# SAM_Dispenser_2.net
KiCad netlist of a schematic drawn in Altium Designer
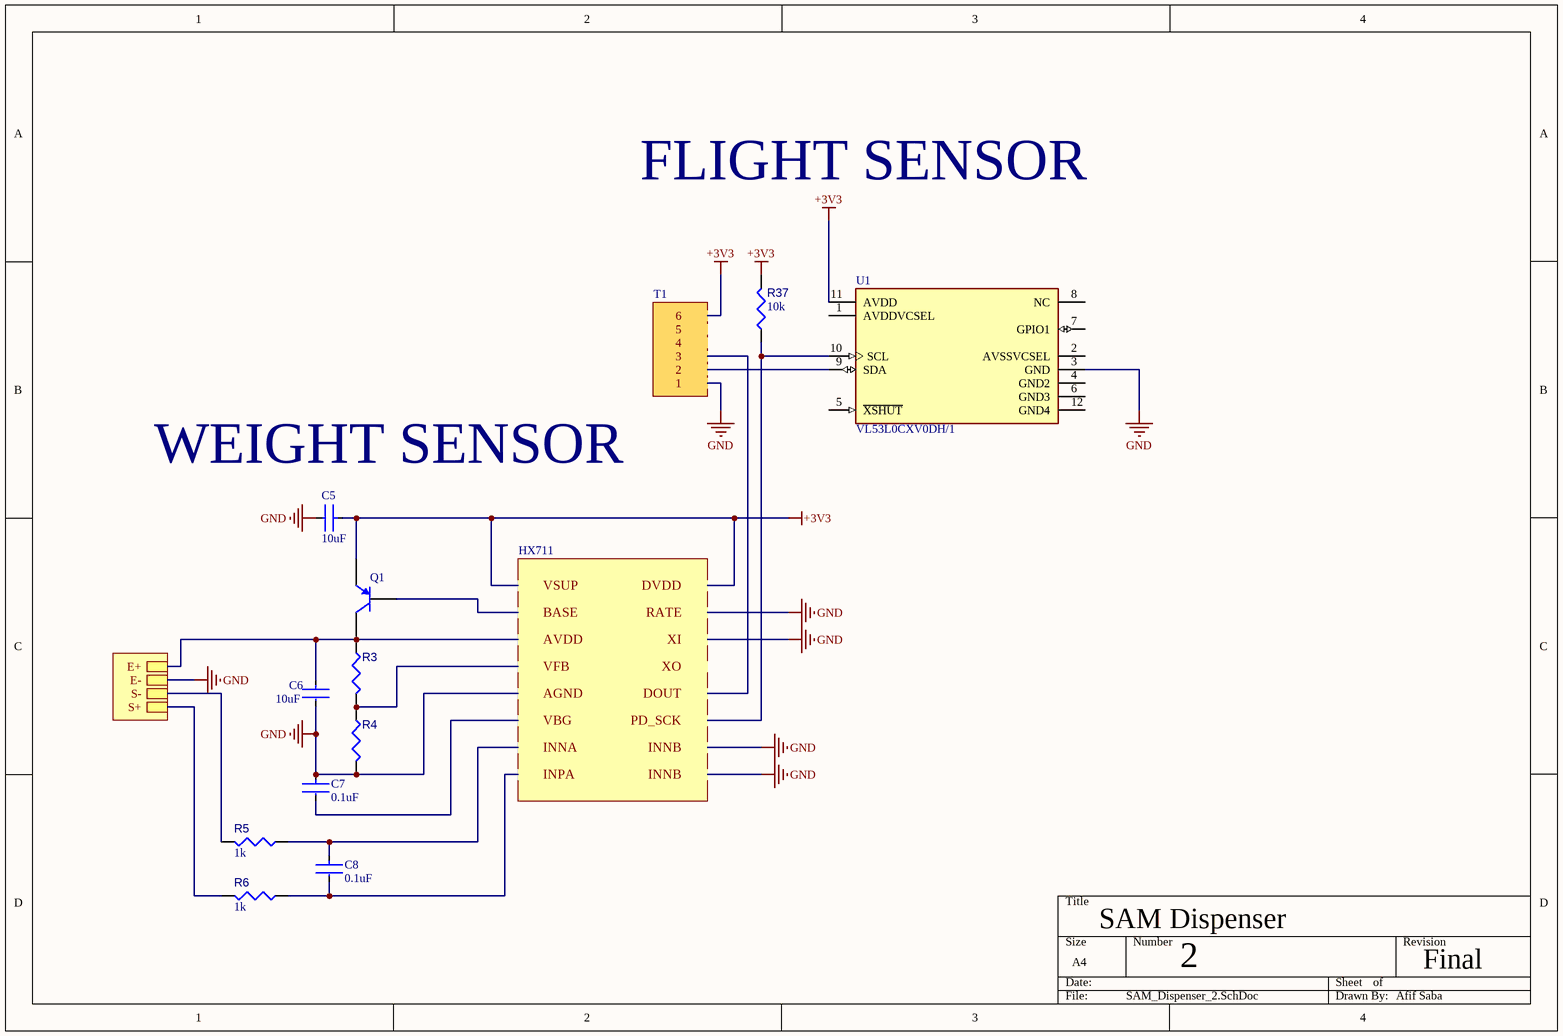
[diagram p0: SAM_Dispenser_2.SchDoc]

(export (version "E")
  (design (tool "Eeschema 10.0.6"))
  (components
    (comp (ref "C5")
      (value "475CKE400M")
      (footprint "4.7uF400V")
      (description "4.7 µF 400 V Aluminum Electrolytic Capacitors Radial, Can 70.547Ohm @ 120Hz 2000 Hrs @ 105°C")
      (fields (field (name "PARAMETER 1") "10uF"))
      (libsource (lib "UNB Workspace") (part "Symbol"))
    )
    (comp (ref "C6")
      (value "475CKE400M")
      (footprint "4.7uF400V")
      (description "4.7 µF 400 V Aluminum Electrolytic Capacitors Radial, Can 70.547Ohm @ 120Hz 2000 Hrs @ 105°C")
      (fields (field (name "PARAMETER 1") "10uF"))
      (libsource (lib "UNB Workspace") (part "Symbol"))
    )
    (comp (ref "C7")
      (value "475CKE400M")
      (footprint "4.7uF400V")
      (description "4.7 µF 400 V Aluminum Electrolytic Capacitors Radial, Can 70.547Ohm @ 120Hz 2000 Hrs @ 105°C")
      (fields (field (name "PARAMETER 1") "0.1uF"))
      (libsource (lib "UNB Workspace") (part "Symbol"))
    )
    (comp (ref "C8")
      (value "475CKE400M")
      (footprint "4.7uF400V")
      (description "4.7 µF 400 V Aluminum Electrolytic Capacitors Radial, Can 70.547Ohm @ 120Hz 2000 Hrs @ 105°C")
      (fields (field (name "PARAMETER 1") "0.1uF"))
      (libsource (lib "UNB Workspace") (part "Symbol"))
    )
    (comp (ref "Q1")
      (value "PN2907ABU")
      (footprint "FAIR-TO-92")
      (description "BJT PNP General Purpose Transistor, 60 V, 800 mA, -55 to 150 degC, 3-Pin TO-92, RoHS, Bulk")
      (fields (field (name "MANUFACTURER") "Fairchild Semiconductor") (field (name "POWER") "625mW"))
      (libsource (lib "UNB Workspace") (part "BJT-PNP-EBC-3"))
    )
    (comp (ref "R3")
      (value "3KR2F")
      (footprint "RESC0402(1005)_L")
      (description "3K 0.063W 1% 0402 (1005 Metric)  SMD")
      (fields (field (name "POWER") "63mW") (field (name "TOLERANCE") "1%"))
      (libsource (lib "UNB Workspace") (part "3KR2F"))
    )
    (comp (ref "R4")
      (value "3KR2F")
      (footprint "RESC0402(1005)_L")
      (description "3K 0.063W 1% 0402 (1005 Metric)  SMD")
      (fields (field (name "POWER") "63mW") (field (name "TOLERANCE") "1%"))
      (libsource (lib "UNB Workspace") (part "3KR2F"))
    )
    (comp (ref "R5")
      (value "3KR2F")
      (footprint "RESC0402(1005)_L")
      (description "3K 0.063W 1% 0402 (1005 Metric)  SMD")
      (fields (field (name "POWER") "63mW") (field (name "TOLERANCE") "1%") (field (name "R34") "1k"))
      (libsource (lib "UNB Workspace") (part "3KR2F"))
    )
    (comp (ref "R6")
      (value "3KR2F")
      (footprint "RESC0402(1005)_L")
      (description "3K 0.063W 1% 0402 (1005 Metric)  SMD")
      (fields (field (name "POWER") "63mW") (field (name "TOLERANCE") "1%") (field (name "R34") "1k"))
      (libsource (lib "UNB Workspace") (part "3KR2F"))
    )
    (comp (ref "R37")
      (value "3KR2F")
      (footprint "RESC0402(1005)_L")
      (description "3K 0.063W 1% 0402 (1005 Metric)  SMD")
      (fields (field (name "POWER") "63mW") (field (name "TOLERANCE") "1%") (field (name "R34") "10k"))
      (libsource (lib "UNB Workspace") (part "3KR2F"))
    )
    (comp (ref "U1")
      (value "VL53L0CXV0DH/1")
      (footprint "FP-LGA-12-MFG")
      (description "SENSOR OPTICAL 200CM I2C")
      (fields
        (field (name "OCTOPART") "https://octopart.com/vl53l0cxv0dh%2F1-stmicroelectronics-71168165")
        (field (name "MANUFACTURER") "STMicroelectronics")
      )
      (libsource (lib "Altium Content Vault") (part "be96beb80d1391f21c16cbc96e60673"))
    )
  )
  (nets
    (net (code "1") (name "+3V3") (class "Default")
      (node (ref "C5") (pin "1") (pinfunction "1_1") (pintype "passive"))
      (node (ref "Q1") (pin "1") (pinfunction "E_1") (pintype "passive"))
      (node (ref "R37") (pin "2") (pinfunction "2_2") (pintype "passive"))
      (node (ref "U1") (pin "11") (pinfunction "AVDD_11") (pintype "power_in"))
    )
    (net (code "2") (name "/2") (class "Default")
      (node (ref "U1") (pin "9") (pinfunction "SDA_9") (pintype "bidirectional"))
    )
    (net (code "6") (name "/AVDD") (class "Default")
      (node (ref "C6") (pin "1") (pinfunction "1_1") (pintype "passive"))
      (node (ref "Q1") (pin "3") (pinfunction "C_3") (pintype "passive"))
      (node (ref "R3") (pin "1") (pinfunction "1_1") (pintype "passive"))
    )
    (net (code "7") (name "/BASE") (class "Default")
      (node (ref "Q1") (pin "2") (pinfunction "B_2") (pintype "passive"))
    )
    (net (code "8") (name "/INNA") (class "Default")
      (node (ref "C8") (pin "1") (pinfunction "1_1") (pintype "passive"))
      (node (ref "R5") (pin "1") (pinfunction "1_1") (pintype "passive"))
    )
    (net (code "9") (name "/INPA") (class "Default")
      (node (ref "C8") (pin "2") (pinfunction "2_2") (pintype "passive"))
      (node (ref "R6") (pin "1") (pinfunction "1_1") (pintype "passive"))
    )
    (net (code "10") (name "/PD_SCK") (class "Default")
      (node (ref "R37") (pin "1") (pinfunction "1_1") (pintype "passive"))
      (node (ref "U1") (pin "10") (pinfunction "SCL_10") (pintype "input"))
    )
    (net (code "11") (name "/S+") (class "Default")
      (node (ref "R6") (pin "2") (pinfunction "2_2") (pintype "passive"))
    )
    (net (code "12") (name "/S-") (class "Default")
      (node (ref "R5") (pin "2") (pinfunction "2_2") (pintype "passive"))
    )
    (net (code "13") (name "/VBG") (class "Default")
      (node (ref "C7") (pin "2") (pinfunction "2_2") (pintype "passive"))
    )
    (net (code "14") (name "/VFB") (class "Default")
      (node (ref "R3") (pin "2") (pinfunction "2_2") (pintype "passive"))
      (node (ref "R4") (pin "1") (pinfunction "1_1") (pintype "passive"))
    )
    (net (code "16") (name "GND") (class "Default")
      (node (ref "C5") (pin "2") (pinfunction "2_2") (pintype "passive"))
      (node (ref "C6") (pin "2") (pinfunction "2_2") (pintype "passive"))
      (node (ref "C7") (pin "1") (pinfunction "1_1") (pintype "passive"))
      (node (ref "R4") (pin "2") (pinfunction "2_2") (pintype "passive"))
      (node (ref "U1") (pin "3") (pinfunction "GND_3") (pintype "power_in"))
    )
    (net (code "17") (name "unconnected-(U1-AVDDVCSEL-Pad1)") (class "Default")
      (node (ref "U1") (pin "1") (pinfunction "AVDDVCSEL_1") (pintype "power_in"))
    )
    (net (code "18") (name "unconnected-(U1-AVSSVCSEL-Pad2)") (class "Default")
      (node (ref "U1") (pin "2") (pinfunction "AVSSVCSEL_2") (pintype "power_in"))
    )
    (net (code "19") (name "unconnected-(U1-GND2-Pad4)") (class "Default")
      (node (ref "U1") (pin "4") (pinfunction "GND2_4") (pintype "power_in"))
    )
    (net (code "20") (name "unconnected-(U1-GND3-Pad6)") (class "Default")
      (node (ref "U1") (pin "6") (pinfunction "GND3_6") (pintype "power_in"))
    )
    (net (code "21") (name "unconnected-(U1-GND4-Pad12)") (class "Default")
      (node (ref "U1") (pin "12") (pinfunction "GND4_12") (pintype "power_in"))
    )
    (net (code "22") (name "unconnected-(U1-GPIO1-Pad7)") (class "Default")
      (node (ref "U1") (pin "7") (pinfunction "GPIO1_7") (pintype "bidirectional"))
    )
    (net (code "23") (name "unconnected-(U1-NC-Pad8)") (class "Default")
      (node (ref "U1") (pin "8") (pinfunction "NC_8") (pintype "passive"))
    )
    (net (code "24") (name "unconnected-(U1-~{XSHUT}-Pad5)") (class "Default")
      (node (ref "U1") (pin "5") (pinfunction "~{XSHUT}_5") (pintype "input"))
    )
  )
)
